# LM_001.net
KiCad netlist of a schematic drawn in Altium Designer
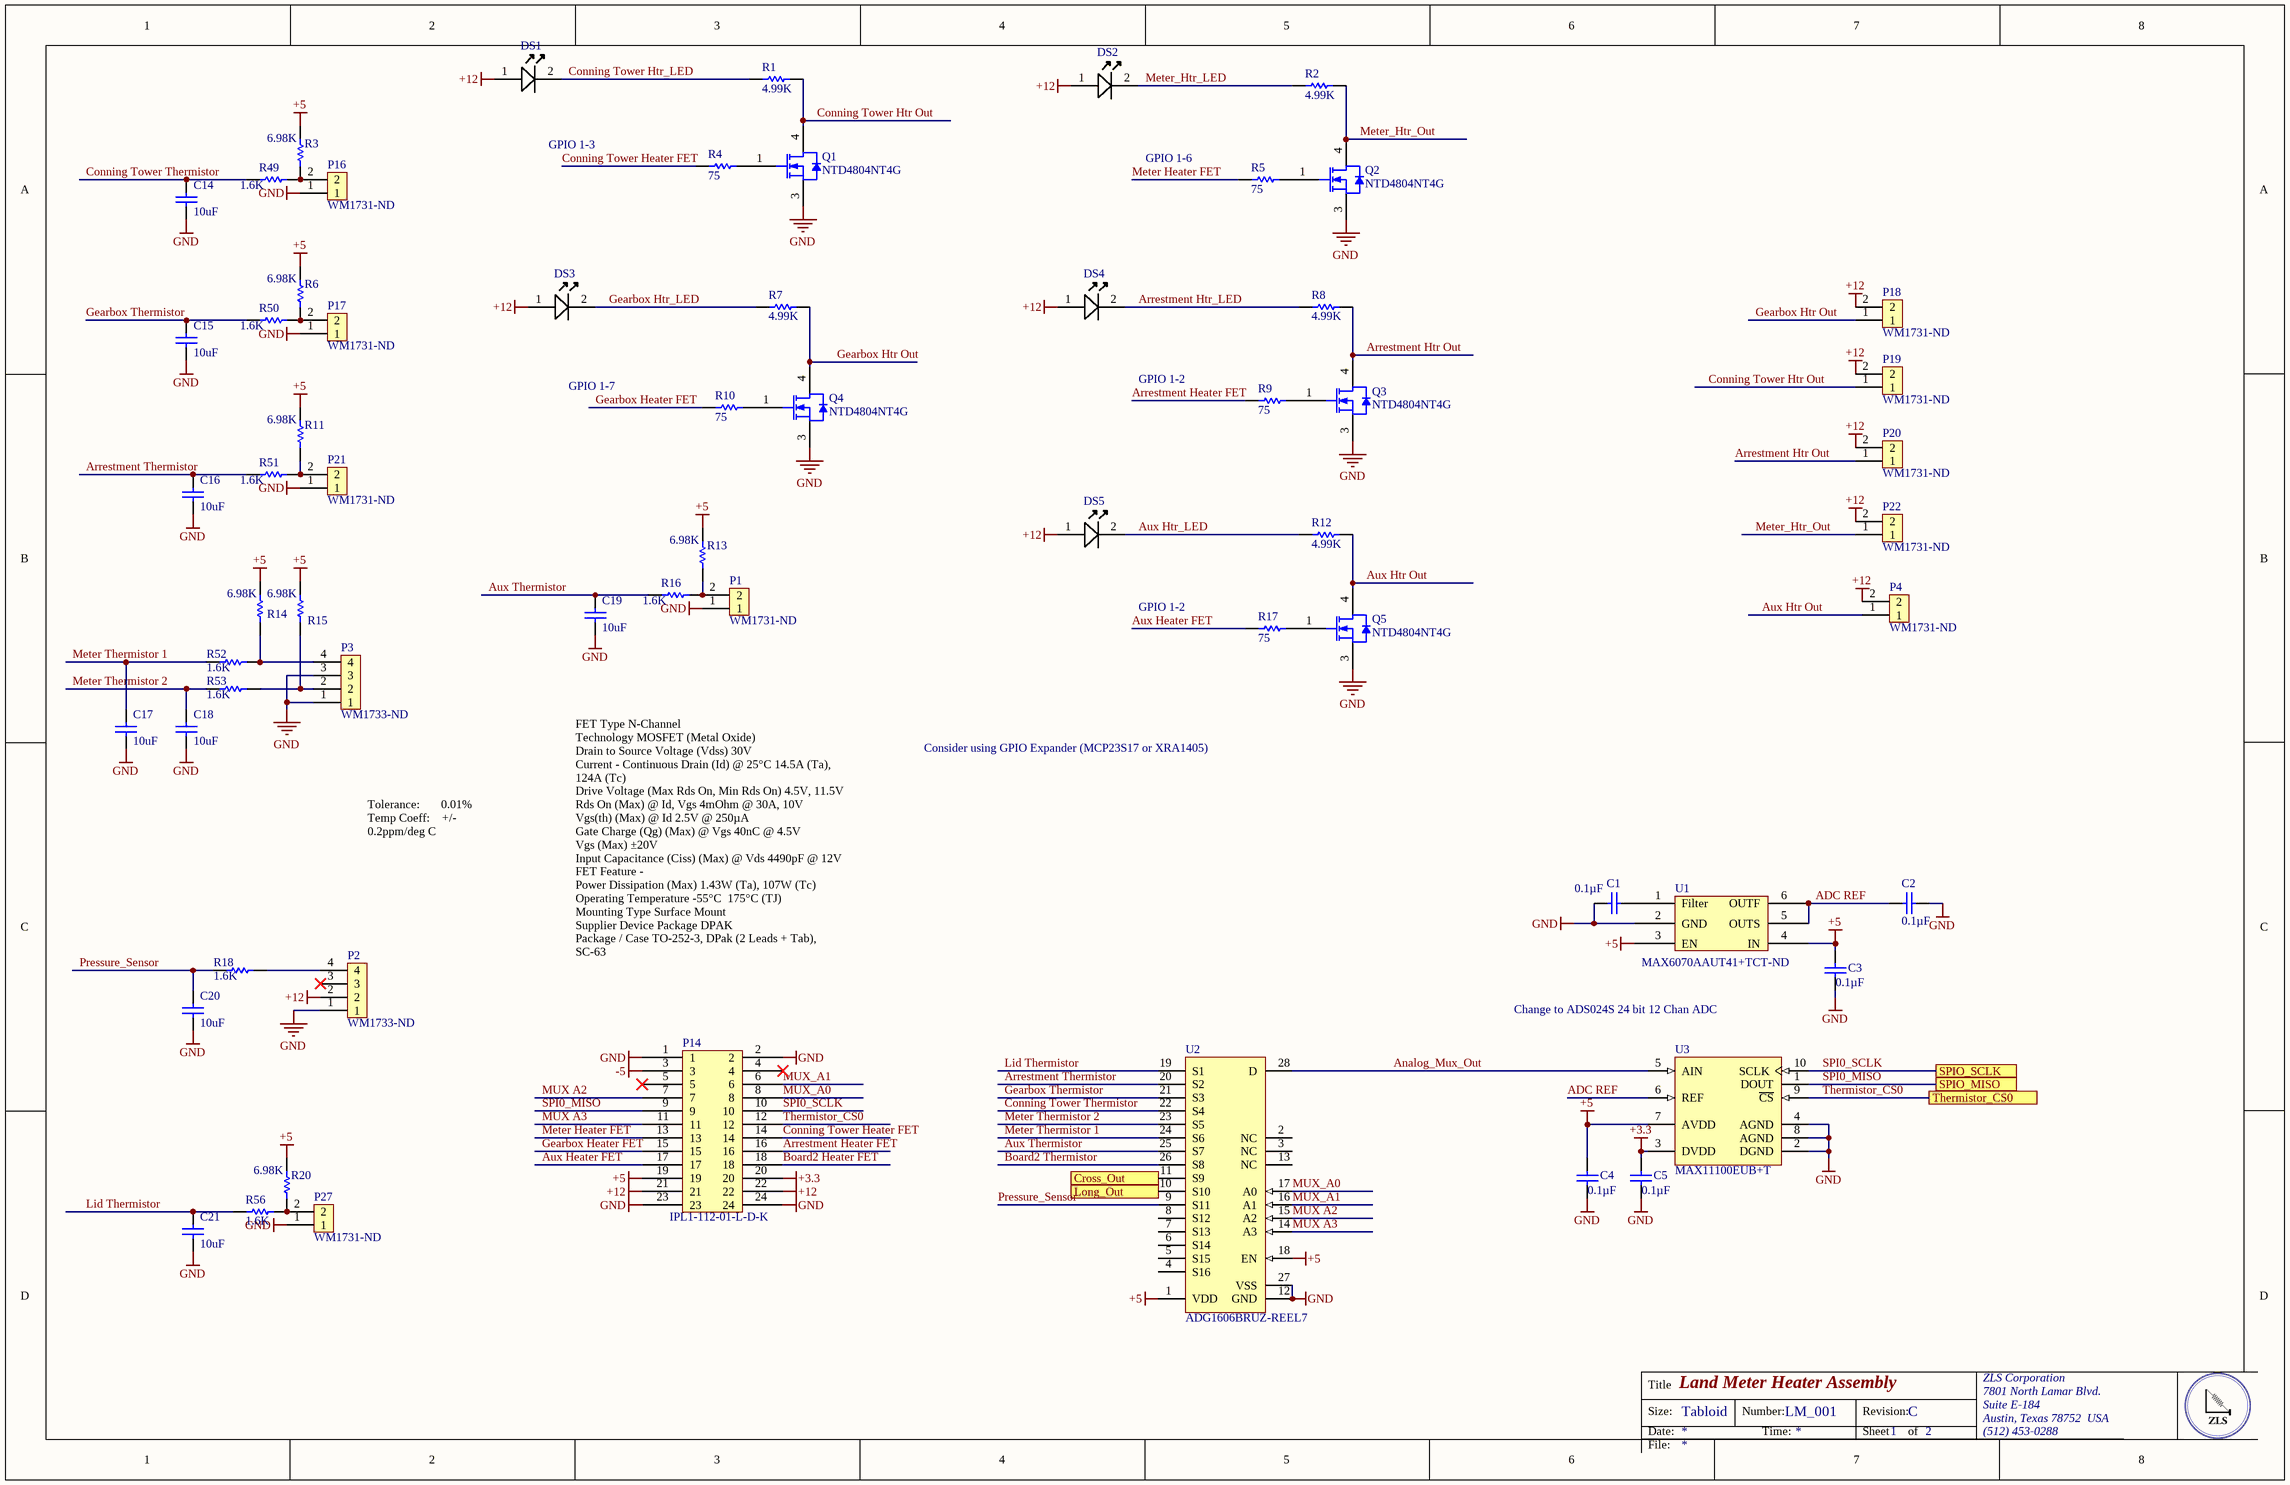
[diagram p0: LM_001.SchDoc]

(export (version "E")
  (design (tool "Eeschema 10.0.6"))
  (components
    (comp (ref "C1")
      (value "CAP CER 0.1UF 25V X7R 0805")
      (footprint "CAPC0805(2012)145_N")
      (fields
        (field (name "MANUFACTURER") "Murata Electronics North America")
        (field (name "MANUFACTURER PART NUMBER") "GRM21BR71E104KA01L")
        (field (name "CAPACITANCE") "0.1µF")
        (field (name "TOLERANCE") "±10%")
      )
      (libsource (lib "Altium Content Vault") (part "CMP-1036-04795-1"))
    )
    (comp (ref "C2")
      (value "CAP CER 0.1UF 25V X7R 0805")
      (footprint "CAPC0805(2012)145_N")
      (fields
        (field (name "MANUFACTURER") "Murata Electronics North America")
        (field (name "MANUFACTURER PART NUMBER") "GRM21BR71E104KA01L")
        (field (name "CAPACITANCE") "0.1µF")
        (field (name "TOLERANCE") "±10%")
      )
      (libsource (lib "Altium Content Vault") (part "CMP-1036-04795-1"))
    )
    (comp (ref "C3")
      (value "CAP CER 0.1UF 25V X7R 0805")
      (footprint "CAPC0805(2012)145_N")
      (fields
        (field (name "MANUFACTURER") "Murata Electronics North America")
        (field (name "MANUFACTURER PART NUMBER") "GRM21BR71E104KA01L")
        (field (name "CAPACITANCE") "0.1µF")
        (field (name "TOLERANCE") "±10%")
      )
      (libsource (lib "Altium Content Vault") (part "CMP-1036-04795-1"))
    )
    (comp (ref "C4")
      (value "CAP CER 0.1UF 25V X7R 0805")
      (footprint "CAPC0805(2012)145_N")
      (fields
        (field (name "MANUFACTURER") "Murata Electronics North America")
        (field (name "MANUFACTURER PART NUMBER") "GRM21BR71E104KA01L")
        (field (name "CAPACITANCE") "0.1µF")
        (field (name "TOLERANCE") "±10%")
      )
      (libsource (lib "Altium Content Vault") (part "CMP-1036-04795-1"))
    )
    (comp (ref "C5")
      (value "CAP CER 0.1UF 25V X7R 0805")
      (footprint "CAPC0805(2012)145_N")
      (fields
        (field (name "MANUFACTURER") "Murata Electronics North America")
        (field (name "MANUFACTURER PART NUMBER") "GRM21BR71E104KA01L")
        (field (name "CAPACITANCE") "0.1µF")
        (field (name "TOLERANCE") "±10%")
      )
      (libsource (lib "Altium Content Vault") (part "CMP-1036-04795-1"))
    )
    (comp (ref "C14")
      (value "10uF")
      (footprint "CAPC0805(2012)145_N")
      (description "CAP CER 10UF 16V X6S 0805")
      (fields
        (field (name "MANUFACTURER") "TDK Corporation")
        (field (name "MANUFACTURER PART NUMBER") "C2012X6S1C106K085AC")
      )
      (libsource (lib "Altium Content Vault") (part "CMP-1036-04795-1"))
    )
    (comp (ref "C15")
      (value "10uF")
      (footprint "CAPC0805(2012)145_N")
      (description "CAP CER 10UF 16V X6S 0805")
      (fields
        (field (name "MANUFACTURER") "TDK Corporation")
        (field (name "MANUFACTURER PART NUMBER") "C2012X6S1C106K085AC")
      )
      (libsource (lib "Altium Content Vault") (part "CMP-1036-04795-1"))
    )
    (comp (ref "C16")
      (value "10uF")
      (footprint "CAPC0805(2012)145_N")
      (description "CAP CER 10UF 16V X6S 0805")
      (fields
        (field (name "MANUFACTURER") "TDK Corporation")
        (field (name "MANUFACTURER PART NUMBER") "C2012X6S1C106K085AC")
      )
      (libsource (lib "Altium Content Vault") (part "CMP-1036-04795-1"))
    )
    (comp (ref "C17")
      (value "10uF")
      (footprint "CAPC0805(2012)145_N")
      (description "CAP CER 10UF 16V X6S 0805")
      (fields
        (field (name "MANUFACTURER") "TDK Corporation")
        (field (name "MANUFACTURER PART NUMBER") "C2012X6S1C106K085AC")
      )
      (libsource (lib "Altium Content Vault") (part "CMP-1036-04795-1"))
    )
    (comp (ref "C18")
      (value "10uF")
      (footprint "CAPC0805(2012)145_N")
      (description "CAP CER 10UF 16V X6S 0805")
      (fields
        (field (name "MANUFACTURER") "TDK Corporation")
        (field (name "MANUFACTURER PART NUMBER") "C2012X6S1C106K085AC")
      )
      (libsource (lib "Altium Content Vault") (part "CMP-1036-04795-1"))
    )
    (comp (ref "C19")
      (value "10uF")
      (footprint "CAPC0805(2012)145_N")
      (description "CAP CER 10UF 16V X6S 0805")
      (fields
        (field (name "MANUFACTURER") "TDK Corporation")
        (field (name "MANUFACTURER PART NUMBER") "C2012X6S1C106K085AC")
      )
      (libsource (lib "Altium Content Vault") (part "CMP-1036-04795-1"))
    )
    (comp (ref "C20")
      (value "10uF")
      (footprint "CAPC0805(2012)145_N")
      (description "CAP CER 10UF 16V X6S 0805")
      (fields
        (field (name "MANUFACTURER") "TDK Corporation")
        (field (name "MANUFACTURER PART NUMBER") "C2012X6S1C106K085AC")
      )
      (libsource (lib "Altium Content Vault") (part "CMP-1036-04795-1"))
    )
    (comp (ref "C21")
      (value "10uF")
      (footprint "CAPC0805(2012)145_N")
      (description "CAP CER 10UF 16V X6S 0805")
      (fields
        (field (name "MANUFACTURER") "TDK Corporation")
        (field (name "MANUFACTURER PART NUMBER") "C2012X6S1C106K085AC")
      )
      (libsource (lib "Altium Content Vault") (part "CMP-1036-04795-1"))
    )
    (comp (ref "DS1")
      (value "LTST-S220KRKT")
      (footprint "0805C_L")
      (description "LED RED CLEAR CHIP SMD R/A")
      (fields (field (name "MANUFACTURER") "Vishay / Lite-On"))
      (libsource (lib "*") (part "LED A/K"))
    )
    (comp (ref "DS2")
      (value "LTST-S220KRKT")
      (footprint "0805C_L")
      (description "LED RED CLEAR CHIP SMD R/A")
      (fields (field (name "MANUFACTURER") "Vishay / Lite-On"))
      (libsource (lib "*") (part "LED A/K"))
    )
    (comp (ref "DS3")
      (value "LTST-S220KRKT")
      (footprint "0805C_L")
      (description "LED RED CLEAR CHIP SMD R/A")
      (fields (field (name "MANUFACTURER") "Vishay / Lite-On"))
      (libsource (lib "*") (part "LED A/K"))
    )
    (comp (ref "DS4")
      (value "LTST-S220KRKT")
      (footprint "0805C_L")
      (description "LED RED CLEAR CHIP SMD R/A")
      (fields (field (name "MANUFACTURER") "Vishay / Lite-On"))
      (libsource (lib "*") (part "LED A/K"))
    )
    (comp (ref "DS5")
      (value "LTST-S220KRKT")
      (footprint "0805C_L")
      (description "LED RED CLEAR CHIP SMD R/A")
      (fields (field (name "MANUFACTURER") "Vishay / Lite-On"))
      (libsource (lib "*") (part "LED A/K"))
    )
    (comp (ref "P1")
      (value "0530470210")
      (footprint "0530470210")
      (description "CONN HEADER VERT 2POS 1.25MM")
      (fields (field (name "SUPPLIER PART NUMBER 1") "WM1731-ND") (field (name "MANUFACTURER") "Molex"))
      (libsource (lib "ZLS_Schematic_lib") (part "0530470210"))
    )
    (comp (ref "P2")
      (value "0530470410")
      (footprint "0530470410")
      (description "CONN HEADER VERT 4POS 1.25MM")
      (fields (field (name "SUPPLIER PART NUMBER 1") "WM1733-ND") (field (name "MANUFACTURER") "Molex"))
      (libsource (lib "ZLS_Schematic_lib") (part "0530470410"))
    )
    (comp (ref "P3")
      (value "0530470410")
      (footprint "0530470410")
      (description "CONN HEADER VERT 4POS 1.25MM")
      (fields (field (name "SUPPLIER PART NUMBER 1") "WM1733-ND") (field (name "MANUFACTURER") "Molex"))
      (libsource (lib "ZLS_Schematic_lib") (part "0530470410"))
    )
    (comp (ref "P4")
      (value "0530470210")
      (footprint "0530470210")
      (description "CONN HEADER VERT 2POS 1.25MM")
      (fields (field (name "SUPPLIER PART NUMBER 1") "WM1731-ND") (field (name "MANUFACTURER") "Molex"))
      (libsource (lib "ZLS_Schematic_lib") (part "0530470210"))
    )
    (comp (ref "P14")
      (value "IPL1-112-01-L-D-K")
      (footprint "IPL1-112-01-F-S-K")
      (fields (field (name "MANUFACTURER") "Samtec Inc."))
      (libsource (lib "ZLS_Schematic_lib") (part "IPL1-112-01-F-S-K"))
    )
    (comp (ref "P16")
      (value "0530470210")
      (footprint "0530470210")
      (description "CONN HEADER VERT 2POS 1.25MM")
      (fields (field (name "SUPPLIER PART NUMBER 1") "WM1731-ND") (field (name "MANUFACTURER") "Molex"))
      (libsource (lib "ZLS_Schematic_lib") (part "0530470210"))
    )
    (comp (ref "P17")
      (value "0530470210")
      (footprint "0530470210")
      (description "CONN HEADER VERT 2POS 1.25MM")
      (fields (field (name "SUPPLIER PART NUMBER 1") "WM1731-ND") (field (name "MANUFACTURER") "Molex"))
      (libsource (lib "ZLS_Schematic_lib") (part "0530470210"))
    )
    (comp (ref "P18")
      (value "0530470210")
      (footprint "0530470210")
      (description "CONN HEADER VERT 2POS 1.25MM")
      (fields (field (name "SUPPLIER PART NUMBER 1") "WM1731-ND") (field (name "MANUFACTURER") "Molex"))
      (libsource (lib "ZLS_Schematic_lib") (part "0530470210"))
    )
    (comp (ref "P19")
      (value "0530470210")
      (footprint "0530470210")
      (description "CONN HEADER VERT 2POS 1.25MM")
      (fields (field (name "SUPPLIER PART NUMBER 1") "WM1731-ND") (field (name "MANUFACTURER") "Molex"))
      (libsource (lib "ZLS_Schematic_lib") (part "0530470210"))
    )
    (comp (ref "P20")
      (value "0530470210")
      (footprint "0530470210")
      (description "CONN HEADER VERT 2POS 1.25MM")
      (fields (field (name "SUPPLIER PART NUMBER 1") "WM1731-ND") (field (name "MANUFACTURER") "Molex"))
      (libsource (lib "ZLS_Schematic_lib") (part "0530470210"))
    )
    (comp (ref "P21")
      (value "0530470210")
      (footprint "0530470210")
      (description "CONN HEADER VERT 2POS 1.25MM")
      (fields (field (name "SUPPLIER PART NUMBER 1") "WM1731-ND") (field (name "MANUFACTURER") "Molex"))
      (libsource (lib "ZLS_Schematic_lib") (part "0530470210"))
    )
    (comp (ref "P22")
      (value "0530470210")
      (footprint "0530470210")
      (description "CONN HEADER VERT 2POS 1.25MM")
      (fields (field (name "SUPPLIER PART NUMBER 1") "WM1731-ND") (field (name "MANUFACTURER") "Molex"))
      (libsource (lib "ZLS_Schematic_lib") (part "0530470210"))
    )
    (comp (ref "P27")
      (value "0530470210")
      (footprint "0530470210")
      (description "CONN HEADER VERT 2POS 1.25MM")
      (fields (field (name "SUPPLIER PART NUMBER 1") "WM1731-ND") (field (name "MANUFACTURER") "Molex"))
      (libsource (lib "ZLS_Schematic_lib") (part "0530470210"))
    )
    (comp (ref "Q1")
      (value "NTD4804NT4G")
      (footprint "ONSC-DPAK-3-369AA-01_V")
      (description "Power MOSFET, 30 V, 117 A, Single N-Channel, 3-Pin DPAK, Pb-Free, Tape and Reel")
      (fields (field (name "MANUFACTURER") "On Semiconductor"))
      (libsource (lib "Altium Content Vault") (part "CMP-1058-00341-1"))
    )
    (comp (ref "Q2")
      (value "NTD4804NT4G")
      (footprint "ONSC-DPAK-3-369AA-01_V")
      (description "Power MOSFET, 30 V, 117 A, Single N-Channel, 3-Pin DPAK, Pb-Free, Tape and Reel")
      (fields (field (name "MANUFACTURER") "On Semiconductor"))
      (libsource (lib "Altium Content Vault") (part "CMP-1058-00341-1"))
    )
    (comp (ref "Q3")
      (value "NTD4804NT4G")
      (footprint "ONSC-DPAK-3-369AA-01_V")
      (description "Power MOSFET, 30 V, 117 A, Single N-Channel, 3-Pin DPAK, Pb-Free, Tape and Reel")
      (fields (field (name "MANUFACTURER") "On Semiconductor"))
      (libsource (lib "Altium Content Vault") (part "CMP-1058-00341-1"))
    )
    (comp (ref "Q4")
      (value "NTD4804NT4G")
      (footprint "ONSC-DPAK-3-369AA-01_V")
      (description "Power MOSFET, 30 V, 117 A, Single N-Channel, 3-Pin DPAK, Pb-Free, Tape and Reel")
      (fields (field (name "MANUFACTURER") "On Semiconductor"))
      (libsource (lib "Altium Content Vault") (part "CMP-1058-00341-1"))
    )
    (comp (ref "Q5")
      (value "NTD4804NT4G")
      (footprint "ONSC-DPAK-3-369AA-01_V")
      (description "Power MOSFET, 30 V, 117 A, Single N-Channel, 3-Pin DPAK, Pb-Free, Tape and Reel")
      (fields (field (name "MANUFACTURER") "On Semiconductor"))
      (libsource (lib "Altium Content Vault") (part "CMP-1058-00341-1"))
    )
    (comp (ref "R1")
      (value "4.99K")
      (footprint "RESC0805(2012)_L")
      (description "RES SMD 4.99K OHM 1% 1/8W 0805")
      (fields
        (field (name "MANUFACTURER") "Vishay Dale")
        (field (name "MANUFACTURER PART NUMBER") "CRCW08054K99FKEA")
      )
      (libsource (lib "Altium Content Vault") (part "CMP-1013-00393-1"))
    )
    (comp (ref "R2")
      (value "4.99K")
      (footprint "RESC0805(2012)_L")
      (description "RES SMD 4.99K OHM 1% 1/8W 0805")
      (fields
        (field (name "MANUFACTURER") "Vishay Dale")
        (field (name "MANUFACTURER PART NUMBER") "CRCW08054K99FKEA")
      )
      (libsource (lib "Altium Content Vault") (part "CMP-1013-00393-1"))
    )
    (comp (ref "R3")
      (value "6.98K")
      (footprint "RESC0805(2012)_N")
      (description "RES SMD 6.98K OHM 1% 1/8W 0805")
      (fields
        (field (name "MANUFACTURER") "Vishay Dale")
        (field (name "MANUFACTURER PART NUMBER") "CRCW08056K98FKEA")
      )
      (libsource (lib "Altium Content Vault") (part "CMP-1013-00606-1"))
    )
    (comp (ref "R4")
      (value "75")
      (footprint "RESC0805(2012)_L")
      (description "RES SMD 75 OHM 1% 1/8W 0805")
      (fields
        (field (name "MANUFACTURER") "Vishay Dale")
        (field (name "MANUFACTURER PART NUMBER") "CRCW080575R0FKTA")
      )
      (libsource (lib "Altium Content Vault") (part "CMP-1013-00393-1"))
    )
    (comp (ref "R5")
      (value "75")
      (footprint "RESC0805(2012)_L")
      (description "RES SMD 75 OHM 1% 1/8W 0805")
      (fields
        (field (name "MANUFACTURER") "Vishay Dale")
        (field (name "MANUFACTURER PART NUMBER") "CRCW080575R0FKTA")
      )
      (libsource (lib "Altium Content Vault") (part "CMP-1013-00393-1"))
    )
    (comp (ref "R6")
      (value "6.98K")
      (footprint "RESC0805(2012)_N")
      (description "RES SMD 6.98K OHM 1% 1/8W 0805")
      (fields
        (field (name "MANUFACTURER") "Vishay Dale")
        (field (name "MANUFACTURER PART NUMBER") "CRCW08056K98FKEA")
      )
      (libsource (lib "Altium Content Vault") (part "CMP-1013-00606-1"))
    )
    (comp (ref "R7")
      (value "4.99K")
      (footprint "RESC0805(2012)_L")
      (description "RES SMD 4.99K OHM 1% 1/8W 0805")
      (fields
        (field (name "MANUFACTURER") "Vishay Dale")
        (field (name "MANUFACTURER PART NUMBER") "CRCW08054K99FKEA")
      )
      (libsource (lib "Altium Content Vault") (part "CMP-1013-00393-1"))
    )
    (comp (ref "R8")
      (value "4.99K")
      (footprint "RESC0805(2012)_L")
      (description "RES SMD 4.99K OHM 1% 1/8W 0805")
      (fields
        (field (name "MANUFACTURER") "Vishay Dale")
        (field (name "MANUFACTURER PART NUMBER") "CRCW08054K99FKEA")
      )
      (libsource (lib "Altium Content Vault") (part "CMP-1013-00393-1"))
    )
    (comp (ref "R9")
      (value "75")
      (footprint "RESC0805(2012)_L")
      (description "RES SMD 75 OHM 1% 1/8W 0805")
      (fields
        (field (name "MANUFACTURER") "Vishay Dale")
        (field (name "MANUFACTURER PART NUMBER") "CRCW080575R0FKTA")
      )
      (libsource (lib "Altium Content Vault") (part "CMP-1013-00393-1"))
    )
    (comp (ref "R10")
      (value "75")
      (footprint "RESC0805(2012)_L")
      (description "RES SMD 75 OHM 1% 1/8W 0805")
      (fields
        (field (name "MANUFACTURER") "Vishay Dale")
        (field (name "MANUFACTURER PART NUMBER") "CRCW080575R0FKTA")
      )
      (libsource (lib "Altium Content Vault") (part "CMP-1013-00393-1"))
    )
    (comp (ref "R11")
      (value "6.98K")
      (footprint "RESC0805(2012)_N")
      (description "RES SMD 6.98K OHM 1% 1/8W 0805")
      (fields
        (field (name "MANUFACTURER") "Vishay Dale")
        (field (name "MANUFACTURER PART NUMBER") "CRCW08056K98FKEA")
      )
      (libsource (lib "Altium Content Vault") (part "CMP-1013-00606-1"))
    )
    (comp (ref "R12")
      (value "4.99K")
      (footprint "RESC0805(2012)_L")
      (description "RES SMD 4.99K OHM 1% 1/8W 0805")
      (fields
        (field (name "MANUFACTURER") "Vishay Dale")
        (field (name "MANUFACTURER PART NUMBER") "CRCW08054K99FKEA")
      )
      (libsource (lib "Altium Content Vault") (part "CMP-1013-00393-1"))
    )
    (comp (ref "R13")
      (value "6.98K")
      (footprint "RESC0805(2012)_N")
      (description "RES SMD 6.98K OHM 1% 1/8W 0805")
      (fields
        (field (name "MANUFACTURER") "Vishay Dale")
        (field (name "MANUFACTURER PART NUMBER") "CRCW08056K98FKEA")
      )
      (libsource (lib "Altium Content Vault") (part "CMP-1013-00606-1"))
    )
    (comp (ref "R14")
      (value "6.98K")
      (footprint "RESC0805(2012)_N")
      (description "RES SMD 6.98K OHM 1% 1/8W 0805")
      (fields
        (field (name "MANUFACTURER") "Vishay Dale")
        (field (name "MANUFACTURER PART NUMBER") "CRCW08056K98FKEA")
      )
      (libsource (lib "Altium Content Vault") (part "CMP-1013-00606-1"))
    )
    (comp (ref "R15")
      (value "6.98K")
      (footprint "RESC0805(2012)_N")
      (description "RES SMD 6.98K OHM 1% 1/8W 0805")
      (fields
        (field (name "MANUFACTURER") "Vishay Dale")
        (field (name "MANUFACTURER PART NUMBER") "CRCW08056K98FKEA")
      )
      (libsource (lib "Altium Content Vault") (part "CMP-1013-00606-1"))
    )
    (comp (ref "R16")
      (value "1.6K")
      (footprint "RESC0805(2012)_N")
      (description "RES SMD 1.6K OHM 1% 1/8W 0805")
      (libsource (lib "Altium Content Vault") (part "CMP-1013-00606-1"))
    )
    (comp (ref "R17")
      (value "75")
      (footprint "RESC0805(2012)_L")
      (description "RES SMD 75 OHM 1% 1/8W 0805")
      (fields
        (field (name "MANUFACTURER") "Vishay Dale")
        (field (name "MANUFACTURER PART NUMBER") "CRCW080575R0FKTA")
      )
      (libsource (lib "Altium Content Vault") (part "CMP-1013-00393-1"))
    )
    (comp (ref "R18")
      (value "1.6K")
      (footprint "RESC0805(2012)_N")
      (description "RES SMD 1.6K OHM 1% 1/8W 0805")
      (libsource (lib "Altium Content Vault") (part "CMP-1013-00606-1"))
    )
    (comp (ref "R20")
      (value "6.98K")
      (footprint "RESC0805(2012)_N")
      (description "RES SMD 6.98K OHM 1% 1/8W 0805")
      (fields
        (field (name "MANUFACTURER") "Vishay Dale")
        (field (name "MANUFACTURER PART NUMBER") "CRCW08056K98FKEA")
      )
      (libsource (lib "Altium Content Vault") (part "CMP-1013-00606-1"))
    )
    (comp (ref "R49")
      (value "1.6K")
      (footprint "RESC0805(2012)_N")
      (description "RES SMD 1.6K OHM 1% 1/8W 0805")
      (libsource (lib "Altium Content Vault") (part "CMP-1013-00606-1"))
    )
    (comp (ref "R50")
      (value "1.6K")
      (footprint "RESC0805(2012)_N")
      (description "RES SMD 1.6K OHM 1% 1/8W 0805")
      (libsource (lib "Altium Content Vault") (part "CMP-1013-00606-1"))
    )
    (comp (ref "R51")
      (value "1.6K")
      (footprint "RESC0805(2012)_N")
      (description "RES SMD 1.6K OHM 1% 1/8W 0805")
      (libsource (lib "Altium Content Vault") (part "CMP-1013-00606-1"))
    )
    (comp (ref "R52")
      (value "1.6K")
      (footprint "RESC0805(2012)_N")
      (description "RES SMD 1.6K OHM 1% 1/8W 0805")
      (libsource (lib "Altium Content Vault") (part "CMP-1013-00606-1"))
    )
    (comp (ref "R53")
      (value "1.6K")
      (footprint "RESC0805(2012)_N")
      (description "RES SMD 1.6K OHM 1% 1/8W 0805")
      (libsource (lib "Altium Content Vault") (part "CMP-1013-00606-1"))
    )
    (comp (ref "R56")
      (value "1.6K")
      (footprint "RESC0805(2012)_N")
      (description "RES SMD 1.6K OHM 1% 1/8W 0805")
      (libsource (lib "Altium Content Vault") (part "CMP-1013-00606-1"))
    )
    (comp (ref "U1")
      (value "MAX6070AAUT41+T")
      (footprint "SOT95P280X445-6N")
      (description "IC VREF SERIES 4.096V SOT23")
      (fields
        (field (name "SUPPLIER PART NUMBER 1") "MAX6070AAUT41+TCT-ND")
        (field (name "MANUFACTURER") "Maxim Integrated")
        (field (name "TOLERANCE") "±0.04%")
      )
      (libsource (lib "ZLS_Schematic_lib") (part "MAX6070AAUT41+T"))
    )
    (comp (ref "U2")
      (value "ADG1606BRUZ-REEL7")
      (footprint "ADI-RU-28_M")
      (description "4.5 Ohm Ron, 16-Channel, +/-5 V,+12 V,+5 V and +3.3 V Multiplexer, 28-pin SOP (RU-28), Reel")
      (fields (field (name "MANUFACTURER") "Analog Devices"))
      (libsource (lib "Altium Content Vault") (part "ADI-ADG1606-RU-28"))
    )
    (comp (ref "U3")
      (value "MAX11100EUB+T")
      (footprint "U10+2_L")
      (description "16-Bit, +5V, 200ksps ADC with 10uA Shutdown, 10-Pin uMAX, -40°C to +85°C, Pb-Free, Tape and Reel")
      (libsource (lib "Altium Content Vault") (part "CON-ADC-MAX11100-IL10"))
    )
  )
  (nets
    (net (code "1") (name "+3.3") (class "Default")
      (node (ref "C5") (pin "1") (pinfunction "1_1") (pintype "passive"))
      (node (ref "P14") (pin "20") (pinfunction "20_20") (pintype "passive"))
      (node (ref "U3") (pin "3") (pinfunction "DVDD_3") (pintype "power_in"))
    )
    (net (code "2") (name "+5") (class "Default")
      (node (ref "C3") (pin "1") (pinfunction "1_1") (pintype "passive"))
      (node (ref "C4") (pin "1") (pinfunction "1_1") (pintype "passive"))
      (node (ref "P14") (pin "19") (pinfunction "19_19") (pintype "passive"))
      (node (ref "R11") (pin "2") (pinfunction "2_2") (pintype "passive"))
      (node (ref "R13") (pin "2") (pinfunction "2_2") (pintype "passive"))
      (node (ref "R14") (pin "2") (pinfunction "2_2") (pintype "passive"))
      (node (ref "R15") (pin "2") (pinfunction "2_2") (pintype "passive"))
      (node (ref "R20") (pin "2") (pinfunction "2_2") (pintype "passive"))
      (node (ref "R3") (pin "2") (pinfunction "2_2") (pintype "passive"))
      (node (ref "R6") (pin "2") (pinfunction "2_2") (pintype "passive"))
      (node (ref "U1") (pin "3") (pinfunction "EN_3") (pintype "passive"))
      (node (ref "U1") (pin "4") (pinfunction "IN_4") (pintype "passive"))
      (node (ref "U2") (pin "1") (pinfunction "VDD_1") (pintype "power_in"))
      (node (ref "U2") (pin "18") (pinfunction "EN_18") (pintype "input"))
      (node (ref "U3") (pin "7") (pinfunction "AVDD_7") (pintype "power_in"))
    )
    (net (code "3") (name "+12") (class "Default")
      (node (ref "DS1") (pin "1") (pinfunction "A_1") (pintype "passive"))
      (node (ref "DS2") (pin "1") (pinfunction "A_1") (pintype "passive"))
      (node (ref "DS3") (pin "1") (pinfunction "A_1") (pintype "passive"))
      (node (ref "DS4") (pin "1") (pinfunction "A_1") (pintype "passive"))
      (node (ref "DS5") (pin "1") (pinfunction "A_1") (pintype "passive"))
      (node (ref "P14") (pin "21") (pinfunction "21_21") (pintype "passive"))
      (node (ref "P14") (pin "22") (pinfunction "22_22") (pintype "passive"))
      (node (ref "P18") (pin "2") (pinfunction "2_2") (pintype "passive"))
      (node (ref "P19") (pin "2") (pinfunction "2_2") (pintype "passive"))
      (node (ref "P2") (pin "2") (pinfunction "2_2") (pintype "passive"))
      (node (ref "P20") (pin "2") (pinfunction "2_2") (pintype "passive"))
      (node (ref "P22") (pin "2") (pinfunction "2_2") (pintype "passive"))
      (node (ref "P4") (pin "2") (pinfunction "2_2") (pintype "passive"))
    )
    (net (code "4") (name "-5") (class "Default")
      (node (ref "P14") (pin "3") (pinfunction "3_3") (pintype "passive"))
    )
    (net (code "5") (name "/ADC REF") (class "Default")
      (node (ref "C2") (pin "1") (pinfunction "1_1") (pintype "passive"))
      (node (ref "U1") (pin "5") (pinfunction "OUTS_5") (pintype "passive"))
      (node (ref "U1") (pin "6") (pinfunction "OUTF_6") (pintype "passive"))
      (node (ref "U3") (pin "6") (pinfunction "REF_6") (pintype "input"))
    )
    (net (code "6") (name "/Analog_Mux_Out") (class "Default")
      (node (ref "U2") (pin "28") (pinfunction "D_28") (pintype "passive"))
      (node (ref "U3") (pin "5") (pinfunction "AIN_5") (pintype "input"))
    )
    (net (code "7") (name "/Arrestment Heater FET") (class "Default")
      (node (ref "P14") (pin "16") (pinfunction "16_16") (pintype "passive"))
      (node (ref "R9") (pin "1") (pinfunction "1_1") (pintype "passive"))
    )
    (net (code "8") (name "/Arrestment Htr Out") (class "Default")
      (node (ref "P20") (pin "1") (pinfunction "1_1") (pintype "passive"))
      (node (ref "Q3") (pin "4") (pinfunction "D_4") (pintype "passive"))
      (node (ref "R8") (pin "1") (pinfunction "1_1") (pintype "passive"))
    )
    (net (code "9") (name "/Arrestment Htr_LED") (class "Default")
      (node (ref "DS4") (pin "2") (pinfunction "K_2") (pintype "passive"))
      (node (ref "R8") (pin "2") (pinfunction "2_2") (pintype "passive"))
    )
    (net (code "10") (name "/Arrestment Thermistor") (class "Default")
      (node (ref "C16") (pin "1") (pinfunction "1_1") (pintype "passive"))
      (node (ref "R51") (pin "2") (pinfunction "2_2") (pintype "passive"))
      (node (ref "U2") (pin "20") (pinfunction "S2_20") (pintype "passive"))
    )
    (net (code "11") (name "/Aux Heater FET") (class "Default")
      (node (ref "P14") (pin "17") (pinfunction "17_17") (pintype "passive"))
      (node (ref "R17") (pin "1") (pinfunction "1_1") (pintype "passive"))
    )
    (net (code "12") (name "/Aux Htr Out") (class "Default")
      (node (ref "P4") (pin "1") (pinfunction "1_1") (pintype "passive"))
      (node (ref "Q5") (pin "4") (pinfunction "D_4") (pintype "passive"))
      (node (ref "R12") (pin "1") (pinfunction "1_1") (pintype "passive"))
    )
    (net (code "13") (name "/Aux Htr_LED") (class "Default")
      (node (ref "DS5") (pin "2") (pinfunction "K_2") (pintype "passive"))
      (node (ref "R12") (pin "2") (pinfunction "2_2") (pintype "passive"))
    )
    (net (code "14") (name "/Aux Thermistor") (class "Default")
      (node (ref "C19") (pin "1") (pinfunction "1_1") (pintype "passive"))
      (node (ref "R16") (pin "2") (pinfunction "2_2") (pintype "passive"))
      (node (ref "U2") (pin "25") (pinfunction "S7_25") (pintype "passive"))
    )
    (net (code "15") (name "/Board2 Heater FET") (class "Default")
      (node (ref "P14") (pin "18") (pinfunction "18_18") (pintype "passive"))
    )
    (net (code "16") (name "/Board2 Thermistor") (class "Default")
      (node (ref "U2") (pin "26") (pinfunction "S8_26") (pintype "passive"))
    )
    (net (code "17") (name "/Conning Tower Heater FET") (class "Default")
      (node (ref "P14") (pin "14") (pinfunction "14_14") (pintype "passive"))
      (node (ref "R4") (pin "1") (pinfunction "1_1") (pintype "passive"))
    )
    (net (code "18") (name "/Conning Tower Htr Out") (class "Default")
      (node (ref "P19") (pin "1") (pinfunction "1_1") (pintype "passive"))
      (node (ref "Q1") (pin "4") (pinfunction "D_4") (pintype "passive"))
      (node (ref "R1") (pin "1") (pinfunction "1_1") (pintype "passive"))
    )
    (net (code "19") (name "/Conning Tower Htr_LED") (class "Default")
      (node (ref "DS1") (pin "2") (pinfunction "K_2") (pintype "passive"))
      (node (ref "R1") (pin "2") (pinfunction "2_2") (pintype "passive"))
    )
    (net (code "20") (name "/Conning Tower Thermistor") (class "Default")
      (node (ref "C14") (pin "1") (pinfunction "1_1") (pintype "passive"))
      (node (ref "R49") (pin "2") (pinfunction "2_2") (pintype "passive"))
      (node (ref "U2") (pin "22") (pinfunction "S4_22") (pintype "passive"))
    )
    (net (code "21") (name "/Cross_Out") (class "Default")
      (node (ref "U2") (pin "11") (pinfunction "S9_11") (pintype "passive"))
    )
    (net (code "22") (name "/Gearbox Heater FET") (class "Default")
      (node (ref "P14") (pin "15") (pinfunction "15_15") (pintype "passive"))
      (node (ref "R10") (pin "1") (pinfunction "1_1") (pintype "passive"))
    )
    (net (code "23") (name "/Gearbox Htr Out") (class "Default")
      (node (ref "P18") (pin "1") (pinfunction "1_1") (pintype "passive"))
      (node (ref "Q4") (pin "4") (pinfunction "D_4") (pintype "passive"))
      (node (ref "R7") (pin "1") (pinfunction "1_1") (pintype "passive"))
    )
    (net (code "24") (name "/Gearbox Htr_LED") (class "Default")
      (node (ref "DS3") (pin "2") (pinfunction "K_2") (pintype "passive"))
      (node (ref "R7") (pin "2") (pinfunction "2_2") (pintype "passive"))
    )
    (net (code "25") (name "/Gearbox Thermistor") (class "Default")
      (node (ref "C15") (pin "1") (pinfunction "1_1") (pintype "passive"))
      (node (ref "R50") (pin "2") (pinfunction "2_2") (pintype "passive"))
      (node (ref "U2") (pin "21") (pinfunction "S3_21") (pintype "passive"))
    )
    (net (code "26") (name "/Lid Thermistor") (class "Default")
      (node (ref "C21") (pin "1") (pinfunction "1_1") (pintype "passive"))
      (node (ref "R56") (pin "2") (pinfunction "2_2") (pintype "passive"))
      (node (ref "U2") (pin "19") (pinfunction "S1_19") (pintype "passive"))
    )
    (net (code "27") (name "/Long_Out") (class "Default")
      (node (ref "U2") (pin "10") (pinfunction "S10_10") (pintype "passive"))
    )
    (net (code "28") (name "/MUX A2") (class "Default")
      (node (ref "P14") (pin "7") (pinfunction "7_7") (pintype "passive"))
      (node (ref "U2") (pin "15") (pinfunction "A2_15") (pintype "input"))
    )
    (net (code "29") (name "/MUX A3") (class "Default")
      (node (ref "P14") (pin "11") (pinfunction "11_11") (pintype "passive"))
      (node (ref "U2") (pin "14") (pinfunction "A3_14") (pintype "input"))
    )
    (net (code "30") (name "/MUX_A0") (class "Default")
      (node (ref "P14") (pin "8") (pinfunction "8_8") (pintype "passive"))
      (node (ref "U2") (pin "17") (pinfunction "A0_17") (pintype "input"))
    )
    (net (code "31") (name "/MUX_A1") (class "Default")
      (node (ref "P14") (pin "6") (pinfunction "6_6") (pintype "passive"))
      (node (ref "U2") (pin "16") (pinfunction "A1_16") (pintype "input"))
    )
    (net (code "32") (name "/Meter Heater FET") (class "Default")
      (node (ref "P14") (pin "13") (pinfunction "13_13") (pintype "passive"))
      (node (ref "R5") (pin "1") (pinfunction "1_1") (pintype "passive"))
    )
    (net (code "33") (name "/Meter Thermistor 1") (class "Default")
      (node (ref "C17") (pin "1") (pinfunction "1_1") (pintype "passive"))
      (node (ref "R52") (pin "2") (pinfunction "2_2") (pintype "passive"))
      (node (ref "U2") (pin "24") (pinfunction "S6_24") (pintype "passive"))
    )
    (net (code "34") (name "/Meter Thermistor 2") (class "Default")
      (node (ref "C18") (pin "1") (pinfunction "1_1") (pintype "passive"))
      (node (ref "R53") (pin "2") (pinfunction "2_2") (pintype "passive"))
      (node (ref "U2") (pin "23") (pinfunction "S5_23") (pintype "passive"))
    )
    (net (code "35") (name "/Meter_Htr_LED") (class "Default")
      (node (ref "DS2") (pin "2") (pinfunction "K_2") (pintype "passive"))
      (node (ref "R2") (pin "2") (pinfunction "2_2") (pintype "passive"))
    )
    (net (code "36") (name "/Meter_Htr_Out") (class "Default")
      (node (ref "P22") (pin "1") (pinfunction "1_1") (pintype "passive"))
      (node (ref "Q2") (pin "4") (pinfunction "D_4") (pintype "passive"))
      (node (ref "R2") (pin "1") (pinfunction "1_1") (pintype "passive"))
    )
    (net (code "37") (name "/Pressure_Sensor") (class "Default")
      (node (ref "C20") (pin "1") (pinfunction "1_1") (pintype "passive"))
      (node (ref "R18") (pin "2") (pinfunction "2_2") (pintype "passive"))
      (node (ref "U2") (pin "9") (pinfunction "S11_9") (pintype "passive"))
    )
    (net (code "38") (name "/SPI0_MISO") (class "Default")
      (node (ref "P14") (pin "9") (pinfunction "9_9") (pintype "passive"))
      (node (ref "U3") (pin "1") (pinfunction "DOUT_1") (pintype "tri_state"))
    )
    (net (code "39") (name "/SPI0_SCLK") (class "Default")
      (node (ref "P14") (pin "10") (pinfunction "10_10") (pintype "passive"))
      (node (ref "U3") (pin "10") (pinfunction "SCLK_10") (pintype "input"))
    )
    (net (code "40") (name "/Thermistor_CS0") (class "Default")
      (node (ref "P14") (pin "12") (pinfunction "12_12") (pintype "passive"))
      (node (ref "U3") (pin "9") (pinfunction "~{CS}_9") (pintype "input"))
    )
    (net (code "41") (name "GND") (class "Default")
      (node (ref "C1") (pin "1") (pinfunction "1_1") (pintype "passive"))
      (node (ref "C14") (pin "2") (pinfunction "2_2") (pintype "passive"))
      (node (ref "C15") (pin "2") (pinfunction "2_2") (pintype "passive"))
      (node (ref "C16") (pin "2") (pinfunction "2_2") (pintype "passive"))
      (node (ref "C17") (pin "2") (pinfunction "2_2") (pintype "passive"))
      (node (ref "C18") (pin "2") (pinfunction "2_2") (pintype "passive"))
      (node (ref "C19") (pin "2") (pinfunction "2_2") (pintype "passive"))
      (node (ref "C2") (pin "2") (pinfunction "2_2") (pintype "passive"))
      (node (ref "C20") (pin "2") (pinfunction "2_2") (pintype "passive"))
      (node (ref "C21") (pin "2") (pinfunction "2_2") (pintype "passive"))
      (node (ref "C3") (pin "2") (pinfunction "2_2") (pintype "passive"))
      (node (ref "C4") (pin "2") (pinfunction "2_2") (pintype "passive"))
      (node (ref "C5") (pin "2") (pinfunction "2_2") (pintype "passive"))
      (node (ref "P1") (pin "1") (pinfunction "1_1") (pintype "passive"))
      (node (ref "P14") (pin "1") (pinfunction "1_1") (pintype "passive"))
      (node (ref "P14") (pin "2") (pinfunction "2_2") (pintype "passive"))
      (node (ref "P14") (pin "23") (pinfunction "23_23") (pintype "passive"))
      (node (ref "P14") (pin "24") (pinfunction "24_24") (pintype "passive"))
      (node (ref "P16") (pin "1") (pinfunction "1_1") (pintype "passive"))
      (node (ref "P17") (pin "1") (pinfunction "1_1") (pintype "passive"))
      (node (ref "P2") (pin "1") (pinfunction "1_1") (pintype "passive"))
      (node (ref "P21") (pin "1") (pinfunction "1_1") (pintype "passive"))
      (node (ref "P27") (pin "1") (pinfunction "1_1") (pintype "passive"))
      (node (ref "P3") (pin "1") (pinfunction "1_1") (pintype "passive"))
      (node (ref "P3") (pin "3") (pinfunction "3_3") (pintype "passive"))
      (node (ref "Q1") (pin "3") (pinfunction "S_3") (pintype "passive"))
      (node (ref "Q2") (pin "3") (pinfunction "S_3") (pintype "passive"))
      (node (ref "Q3") (pin "3") (pinfunction "S_3") (pintype "passive"))
      (node (ref "Q4") (pin "3") (pinfunction "S_3") (pintype "passive"))
      (node (ref "Q5") (pin "3") (pinfunction "S_3") (pintype "passive"))
      (node (ref "U1") (pin "2") (pinfunction "GND_2") (pintype "passive"))
      (node (ref "U2") (pin "12") (pinfunction "GND_12") (pintype "power_in"))
      (node (ref "U2") (pin "27") (pinfunction "VSS_27") (pintype "power_in"))
      (node (ref "U3") (pin "2") (pinfunction "DGND_2") (pintype "power_in"))
      (node (ref "U3") (pin "4") (pinfunction "AGND_4") (pintype "power_in"))
      (node (ref "U3") (pin "8") (pinfunction "AGND_8") (pintype "power_in"))
    )
    (net (code "42") (name "Net-(P1-Pad2)") (class "Default")
      (node (ref "P1") (pin "2") (pinfunction "2_2") (pintype "passive"))
      (node (ref "R13") (pin "1") (pinfunction "1_1") (pintype "passive"))
      (node (ref "R16") (pin "1") (pinfunction "1_1") (pintype "passive"))
    )
    (net (code "43") (name "Net-(P2-Pad4)") (class "Default")
      (node (ref "P2") (pin "4") (pinfunction "4_4") (pintype "passive"))
      (node (ref "R18") (pin "1") (pinfunction "1_1") (pintype "passive"))
    )
    (net (code "44") (name "Net-(P3-Pad2)") (class "Default")
      (node (ref "P3") (pin "2") (pinfunction "2_2") (pintype "passive"))
      (node (ref "R15") (pin "1") (pinfunction "1_1") (pintype "passive"))
      (node (ref "R53") (pin "1") (pinfunction "1_1") (pintype "passive"))
    )
    (net (code "45") (name "Net-(P3-Pad4)") (class "Default")
      (node (ref "P3") (pin "4") (pinfunction "4_4") (pintype "passive"))
      (node (ref "R14") (pin "1") (pinfunction "1_1") (pintype "passive"))
      (node (ref "R52") (pin "1") (pinfunction "1_1") (pintype "passive"))
    )
    (net (code "46") (name "Net-(P16-Pad2)") (class "Default")
      (node (ref "P16") (pin "2") (pinfunction "2_2") (pintype "passive"))
      (node (ref "R3") (pin "1") (pinfunction "1_1") (pintype "passive"))
      (node (ref "R49") (pin "1") (pinfunction "1_1") (pintype "passive"))
    )
    (net (code "47") (name "Net-(P17-Pad2)") (class "Default")
      (node (ref "P17") (pin "2") (pinfunction "2_2") (pintype "passive"))
      (node (ref "R50") (pin "1") (pinfunction "1_1") (pintype "passive"))
      (node (ref "R6") (pin "1") (pinfunction "1_1") (pintype "passive"))
    )
    (net (code "48") (name "Net-(P21-Pad2)") (class "Default")
      (node (ref "P21") (pin "2") (pinfunction "2_2") (pintype "passive"))
      (node (ref "R11") (pin "1") (pinfunction "1_1") (pintype "passive"))
      (node (ref "R51") (pin "1") (pinfunction "1_1") (pintype "passive"))
    )
    (net (code "49") (name "Net-(P27-Pad2)") (class "Default")
      (node (ref "P27") (pin "2") (pinfunction "2_2") (pintype "passive"))
      (node (ref "R20") (pin "1") (pinfunction "1_1") (pintype "passive"))
      (node (ref "R56") (pin "1") (pinfunction "1_1") (pintype "passive"))
    )
    (net (code "50") (name "Net-(Q1-G)") (class "Default")
      (node (ref "Q1") (pin "1") (pinfunction "G_1") (pintype "passive"))
      (node (ref "R4") (pin "2") (pinfunction "2_2") (pintype "passive"))
    )
    (net (code "51") (name "Net-(Q2-G)") (class "Default")
      (node (ref "Q2") (pin "1") (pinfunction "G_1") (pintype "passive"))
      (node (ref "R5") (pin "2") (pinfunction "2_2") (pintype "passive"))
    )
    (net (code "52") (name "Net-(Q3-G)") (class "Default")
      (node (ref "Q3") (pin "1") (pinfunction "G_1") (pintype "passive"))
      (node (ref "R9") (pin "2") (pinfunction "2_2") (pintype "passive"))
    )
    (net (code "53") (name "Net-(Q4-G)") (class "Default")
      (node (ref "Q4") (pin "1") (pinfunction "G_1") (pintype "passive"))
      (node (ref "R10") (pin "2") (pinfunction "2_2") (pintype "passive"))
    )
    (net (code "54") (name "Net-(Q5-G)") (class "Default")
      (node (ref "Q5") (pin "1") (pinfunction "G_1") (pintype "passive"))
      (node (ref "R17") (pin "2") (pinfunction "2_2") (pintype "passive"))
    )
    (net (code "55") (name "Net-(U1-Filter)") (class "Default")
      (node (ref "C1") (pin "2") (pinfunction "2_2") (pintype "passive"))
      (node (ref "U1") (pin "1") (pinfunction "Filter_1") (pintype "passive"))
    )
    (net (code "56") (name "unconnected-(P2-Pad3)") (class "Default")
      (node (ref "P2") (pin "3") (pinfunction "3_3") (pintype "passive+no_connect"))
    )
    (net (code "57") (name "unconnected-(P14-Pad4)") (class "Default")
      (node (ref "P14") (pin "4") (pinfunction "4_4") (pintype "passive+no_connect"))
    )
    (net (code "58") (name "unconnected-(P14-Pad5)") (class "Default")
      (node (ref "P14") (pin "5") (pinfunction "5_5") (pintype "passive+no_connect"))
    )
    (net (code "59") (name "unconnected-(U2-NC-Pad2)") (class "Default")
      (node (ref "U2") (pin "2") (pinfunction "NC_2") (pintype "passive"))
    )
    (net (code "60") (name "unconnected-(U2-NC-Pad3)") (class "Default")
      (node (ref "U2") (pin "3") (pinfunction "NC_3") (pintype "passive"))
    )
    (net (code "61") (name "unconnected-(U2-NC-Pad13)") (class "Default")
      (node (ref "U2") (pin "13") (pinfunction "NC_13") (pintype "passive"))
    )
    (net (code "62") (name "unconnected-(U2-S12-Pad8)") (class "Default")
      (node (ref "U2") (pin "8") (pinfunction "S12_8") (pintype "passive"))
    )
    (net (code "63") (name "unconnected-(U2-S13-Pad7)") (class "Default")
      (node (ref "U2") (pin "7") (pinfunction "S13_7") (pintype "passive"))
    )
    (net (code "64") (name "unconnected-(U2-S14-Pad6)") (class "Default")
      (node (ref "U2") (pin "6") (pinfunction "S14_6") (pintype "passive"))
    )
    (net (code "65") (name "unconnected-(U2-S15-Pad5)") (class "Default")
      (node (ref "U2") (pin "5") (pinfunction "S15_5") (pintype "passive"))
    )
    (net (code "66") (name "unconnected-(U2-S16-Pad4)") (class "Default")
      (node (ref "U2") (pin "4") (pinfunction "S16_4") (pintype "passive"))
    )
  )
)
